# Motors.net
KiCad netlist of a schematic drawn in Altium Designer
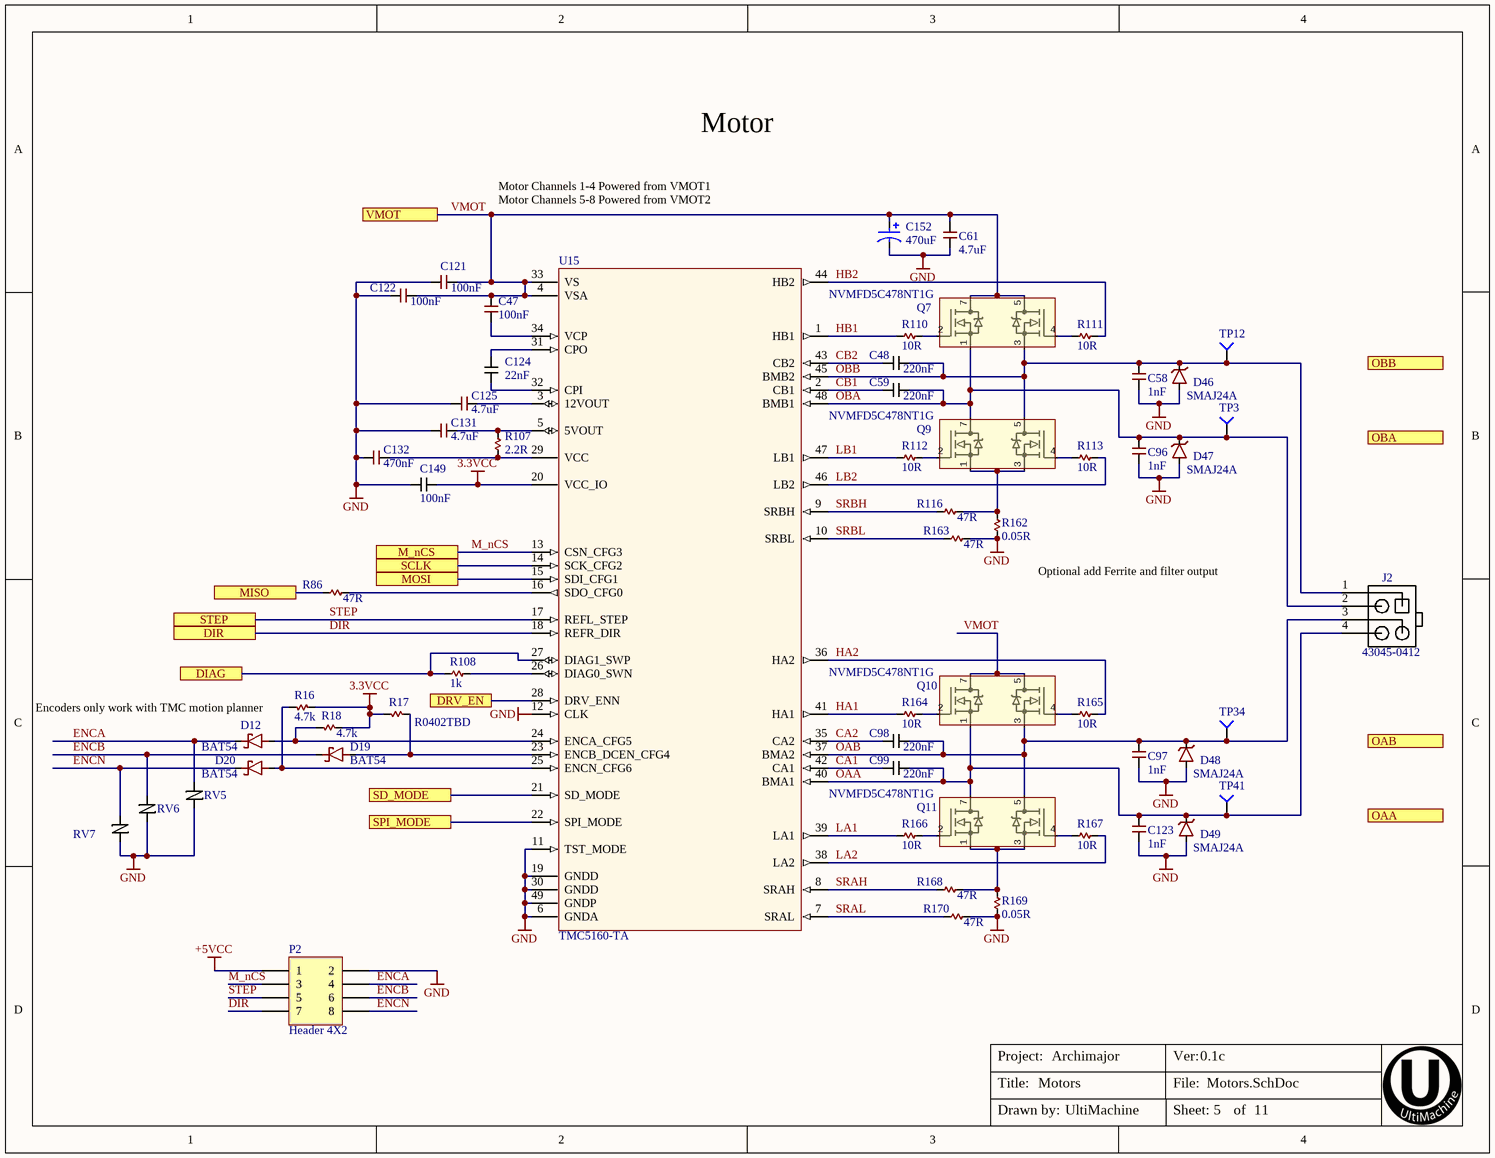
[diagram p0: Motors.SchDoc]

(export (version "E")
  (design (tool "Eeschema 10.0.6"))
  (components
    (comp (ref "C47")
      (value "100nF")
      (footprint "C0603")
      (description "CAP CER 0603 100nF 50V 10% X7R")
      (fields (field (name "MANUFACTURER") "Kemet") (field (name "PART") "C0603C104K5RACTU"))
      (libsource (lib "Capacitors") (part "100nF 0603 50V X7R"))
    )
    (comp (ref "C48")
      (value "220nF")
      (footprint "C0603")
      (description "CAP CER 0.22UF 50V X7R 0603")
      (fields (field (name "MANUFACTURER") "TDK") (field (name "PART") "CGA3E3X7R1H224K080AB"))
      (libsource (lib "Capacitors") (part "220nF 50V X7R 0603"))
    )
    (comp (ref "C58")
      (value "1nF")
      (footprint "C0603")
      (description "CAP CER 0603  1nF 50v 10% X7R")
      (fields (field (name "MANUFACTURER") "Kemet") (field (name "PART") "C0603C102K5RACTU"))
      (libsource (lib "Capacitors") (part "1nF 50V X7R 0603"))
    )
    (comp (ref "C59")
      (value "220nF")
      (footprint "C0603")
      (description "CAP CER 0.22UF 50V X7R 0603")
      (fields (field (name "MANUFACTURER") "TDK") (field (name "PART") "CGA3E3X7R1H224K080AB"))
      (libsource (lib "Capacitors") (part "220nF 50V X7R 0603"))
    )
    (comp (ref "C61")
      (value "4.7uF")
      (footprint "C1206")
      (description "CAP CER 1206 4.7uF 50V 10% X5R")
      (fields (field (name "MANUFACTURER") "Kemet") (field (name "PART") "C1206C475K5PACTU"))
      (libsource (lib "Capacitors") (part "4.7uF 1206 50V X5R"))
    )
    (comp (ref "C96")
      (value "1nF")
      (footprint "C0603")
      (description "CAP CER 0603  1nF 50v 10% X7R")
      (fields (field (name "MANUFACTURER") "Kemet") (field (name "PART") "C0603C102K5RACTU"))
      (libsource (lib "Capacitors") (part "1nF 50V X7R 0603"))
    )
    (comp (ref "C97")
      (value "1nF")
      (footprint "C0603")
      (description "CAP CER 0603  1nF 50v 10% X7R")
      (fields (field (name "MANUFACTURER") "Kemet") (field (name "PART") "C0603C102K5RACTU"))
      (libsource (lib "Capacitors") (part "1nF 50V X7R 0603"))
    )
    (comp (ref "C98")
      (value "220nF")
      (footprint "C0603")
      (description "CAP CER 0.22UF 50V X7R 0603")
      (fields (field (name "MANUFACTURER") "TDK") (field (name "PART") "CGA3E3X7R1H224K080AB"))
      (libsource (lib "Capacitors") (part "220nF 50V X7R 0603"))
    )
    (comp (ref "C99")
      (value "220nF")
      (footprint "C0603")
      (description "CAP CER 0.22UF 50V X7R 0603")
      (fields (field (name "MANUFACTURER") "TDK") (field (name "PART") "CGA3E3X7R1H224K080AB"))
      (libsource (lib "Capacitors") (part "220nF 50V X7R 0603"))
    )
    (comp (ref "C121")
      (value "100nF")
      (footprint "C0603")
      (description "CAP CER 0603 100nF 50V 10% X7R")
      (fields (field (name "MANUFACTURER") "Kemet") (field (name "PART") "C0603C104K5RACTU"))
      (libsource (lib "Capacitors") (part "100nF 0603 50V X7R"))
    )
    (comp (ref "C122")
      (value "100nF")
      (footprint "C0603")
      (description "CAP CER 0603 100nF 50V 10% X7R")
      (fields (field (name "MANUFACTURER") "Kemet") (field (name "PART") "C0603C104K5RACTU"))
      (libsource (lib "Capacitors") (part "100nF 0603 50V X7R"))
    )
    (comp (ref "C123")
      (value "1nF")
      (footprint "C0603")
      (description "CAP CER 0603  1nF 50v 10% X7R")
      (fields (field (name "MANUFACTURER") "Kemet") (field (name "PART") "C0603C102K5RACTU"))
      (libsource (lib "Capacitors") (part "1nF 50V X7R 0603"))
    )
    (comp (ref "C124")
      (value "22nF")
      (footprint "C0603")
      (description "CAP CER 0.022UF 100V X7R 0603")
      (fields (field (name "MANUFACTURER") "Kemet") (field (name "PART") "C0603C223K1RACTU"))
      (libsource (lib "Capacitors") (part "22nF 100V X7R 0603"))
    )
    (comp (ref "C125")
      (value "4.7uF")
      (footprint "C1206")
      (description "CAP CER 1206 4.7uF 50V 10% X5R")
      (fields (field (name "MANUFACTURER") "Kemet") (field (name "PART") "C1206C475K5PACTU"))
      (libsource (lib "Capacitors") (part "4.7uF 1206 50V X5R"))
    )
    (comp (ref "C131")
      (value "4.7uF")
      (footprint "C0603")
      (description "CAP CER 4.7UF 6.3V X7R 0603")
      (fields (field (name "MANUFACTURER") "Samsung") (field (name "PART") "CL10B475KQ8NQNC"))
      (libsource (lib "Capacitors") (part "4.7uF 0603 6.3V X7R"))
    )
    (comp (ref "C132")
      (value "470nF")
      (footprint "C0402")
      (description "470nF 6.3v C0402 - GRM155R60J474KE19D")
      (fields (field (name "TOLERANCE") "10%") (field (name "MANUFACTURER") "Murata"))
      (libsource (lib "Capacitors") (part "470nF 0402 6.3V X5R"))
    )
    (comp (ref "C149")
      (value "100nF")
      (footprint "C0201 Large Pads")
      (description "CAP CER 0.1UF 6.3V 10% X5R 0201")
      (fields (field (name "MANUFACTURER") "Samsung") (field (name "TOLERANCE") "10%"))
      (libsource (lib "Capacitors") (part "100nF 6.3V X5R 0201"))
    )
    (comp (ref "C152")
      (value "470uF")
      (footprint "CAP16x17")
      (description "CAP ALUM 470UF 20% 50V SMD")
      (fields (field (name "MANUFACTURER") "Nichicon") (field (name "PART") "UCZ1H471MNQ1MS"))
      (libsource (lib "Capacitors") (part "470uF Al-El 50V 80mOhms 16-18mmD"))
    )
    (comp (ref "D12")
      (value "BAT54")
      (footprint "SOD523_IPC")
      (description "DIODE SCHOTTKY 30V 200MA SOD523")
      (fields (field (name "MANUFACTURER") "Diodes Incorporated") (field (name "PART") "BAT54WX-TP"))
      (libsource (lib "Diodes") (part "BAT54WX"))
    )
    (comp (ref "D19")
      (value "BAT54")
      (footprint "SOD523_IPC")
      (description "DIODE SCHOTTKY 30V 200MA SOD523")
      (fields (field (name "MANUFACTURER") "Diodes Incorporated") (field (name "PART") "BAT54WX-TP"))
      (libsource (lib "Diodes") (part "BAT54WX"))
    )
    (comp (ref "D20")
      (value "BAT54")
      (footprint "SOD523_IPC")
      (description "DIODE SCHOTTKY 30V 200MA SOD523")
      (fields (field (name "MANUFACTURER") "Diodes Incorporated") (field (name "PART") "BAT54WX-TP"))
      (libsource (lib "Diodes") (part "BAT54WX"))
    )
    (comp (ref "D46")
      (value "SMAJ24A")
      (footprint "SMA-SM")
      (description "TVS DIODE 24V 38.9V SMA")
      (fields (field (name "MANUFACTURER") "Bourns Inc"))
      (libsource (lib "Diodes") (part "SMAJ24A"))
    )
    (comp (ref "D47")
      (value "SMAJ24A")
      (footprint "SMA-SM")
      (description "TVS DIODE 24V 38.9V SMA")
      (fields (field (name "MANUFACTURER") "Bourns Inc"))
      (libsource (lib "Diodes") (part "SMAJ24A"))
    )
    (comp (ref "D48")
      (value "SMAJ24A")
      (footprint "SMA-SM")
      (description "TVS DIODE 24V 38.9V SMA")
      (fields (field (name "MANUFACTURER") "Bourns Inc"))
      (libsource (lib "Diodes") (part "SMAJ24A"))
    )
    (comp (ref "D49")
      (value "SMAJ24A")
      (footprint "SMA-SM")
      (description "TVS DIODE 24V 38.9V SMA")
      (fields (field (name "MANUFACTURER") "Bourns Inc"))
      (libsource (lib "Diodes") (part "SMAJ24A"))
    )
    (comp (ref "J2")
      (value "43045-0412")
      (footprint "43045-0412")
      (description "Conn - 3mm Pitch Fixed")
      (fields (field (name "MANUFACTURER") "Molex"))
      (libsource (lib "Connectors") (part "Micro-Fit THT 4pos 3mm"))
    )
    (comp (ref "P2")
      (value "Header 4X2")
      (footprint "HDR2X4")
      (description "Header, 4-Pin, Dual row")
      (fields (field (name "PUBLISHER") "Altium Limited"))
      (libsource (lib "Miscellaneous Connectors") (part "Header 4X2"))
    )
    (comp (ref "Q7")
      (value "NVMFD5C478NT1G")
      (footprint "SO8FL-Dual (DFN8 5x6, 1.26P Dual Flag)")
      (description "40V 17 MOHM T6 S08FL DUAL")
      (fields (field (name "MANUFACTURER") "ON Semiconductor") (field (name "TOLERANCE") "-NA-"))
      (libsource (lib "Transistors") (part "NVMFD5C478NT1G"))
    )
    (comp (ref "Q9")
      (value "NVMFD5C478NT1G")
      (footprint "SO8FL-Dual (DFN8 5x6, 1.26P Dual Flag)")
      (description "40V 17 MOHM T6 S08FL DUAL")
      (fields (field (name "MANUFACTURER") "ON Semiconductor") (field (name "TOLERANCE") "-NA-"))
      (libsource (lib "Transistors") (part "NVMFD5C478NT1G"))
    )
    (comp (ref "Q10")
      (value "NVMFD5C478NT1G")
      (footprint "SO8FL-Dual (DFN8 5x6, 1.26P Dual Flag)")
      (description "40V 17 MOHM T6 S08FL DUAL")
      (fields (field (name "MANUFACTURER") "ON Semiconductor") (field (name "TOLERANCE") "-NA-"))
      (libsource (lib "Transistors") (part "NVMFD5C478NT1G"))
    )
    (comp (ref "Q11")
      (value "NVMFD5C478NT1G")
      (footprint "SO8FL-Dual (DFN8 5x6, 1.26P Dual Flag)")
      (description "40V 17 MOHM T6 S08FL DUAL")
      (fields (field (name "MANUFACTURER") "ON Semiconductor") (field (name "TOLERANCE") "-NA-"))
      (libsource (lib "Transistors") (part "NVMFD5C478NT1G"))
    )
    (comp (ref "R16")
      (value "4.7k")
      (footprint "R0402")
      (description "RES SMD 4.7K OHM 1% 1/16W 0402")
      (fields (field (name "MANUFACTURER") "YAGEO") (field (name "PART") "RC0402FR-074K7L"))
      (libsource (lib "Resistors") (part "4.7k 1% 0402"))
    )
    (comp (ref "R17")
      (value "R0402TBD")
      (footprint "R0402")
      (description "Resistor")
      (libsource (lib "Resistors") (part "R0402TBD"))
    )
    (comp (ref "R18")
      (value "4.7k")
      (footprint "R0402")
      (description "RES SMD 4.7K OHM 1% 1/16W 0402")
      (fields (field (name "MANUFACTURER") "YAGEO") (field (name "PART") "RC0402FR-074K7L"))
      (libsource (lib "Resistors") (part "4.7k 1% 0402"))
    )
    (comp (ref "R86")
      (value "47R")
      (footprint "R0402")
      (description "RES 47 OHM 1% 1/16W 0402")
      (fields (field (name "MANUFACTURER") "Vishay Dale") (field (name "TOLERANCE") "+/- 1%"))
      (libsource (lib "Resistors") (part "47R 1% 0402"))
    )
    (comp (ref "R107")
      (value "2.2R")
      (footprint "R0402")
      (description "RES SMD 2.2 OHM 5% 1/16W 0402")
      (fields (field (name "MANUFACTURER") "Yageo") (field (name "TOLERANCE") "+/- 5%"))
      (libsource (lib "Resistors") (part "2.2R 5% 0402"))
    )
    (comp (ref "R108")
      (value "1k")
      (footprint "R0402")
      (description "RES 0402 1k 63mW 1%")
      (fields (field (name "MANUFACTURER") "Yageo") (field (name "PART") "RC0402FR-071KL"))
      (libsource (lib "Resistors") (part "1k 1% 0402"))
    )
    (comp (ref "R110")
      (value "10R")
      (footprint "R0402")
      (description "RES SMD 10 OHM 1% 1/16W 0402")
      (fields (field (name "MANUFACTURER") "Yageo") (field (name "PART") "RC0402FR-0710RL"))
      (libsource (lib "Resistors") (part "10R 1% 0402"))
    )
    (comp (ref "R111")
      (value "10R")
      (footprint "R0402")
      (description "RES SMD 10 OHM 1% 1/16W 0402")
      (fields (field (name "MANUFACTURER") "Yageo") (field (name "PART") "RC0402FR-0710RL"))
      (libsource (lib "Resistors") (part "10R 1% 0402"))
    )
    (comp (ref "R112")
      (value "10R")
      (footprint "R0402")
      (description "RES SMD 10 OHM 1% 1/16W 0402")
      (fields (field (name "MANUFACTURER") "Yageo") (field (name "PART") "RC0402FR-0710RL"))
      (libsource (lib "Resistors") (part "10R 1% 0402"))
    )
    (comp (ref "R113")
      (value "10R")
      (footprint "R0402")
      (description "RES SMD 10 OHM 1% 1/16W 0402")
      (fields (field (name "MANUFACTURER") "Yageo") (field (name "PART") "RC0402FR-0710RL"))
      (libsource (lib "Resistors") (part "10R 1% 0402"))
    )
    (comp (ref "R116")
      (value "47R")
      (footprint "R0402")
      (description "RES 47 OHM 1% 1/16W 0402")
      (fields (field (name "MANUFACTURER") "Vishay Dale") (field (name "TOLERANCE") "+/- 1%"))
      (libsource (lib "Resistors") (part "47R 1% 0402"))
    )
    (comp (ref "R162")
      (value "0.05R")
      (footprint "R2512")
      (description "RES 0.05 OHM 1% 2W 2512")
      (fields (field (name "MANUFACTURER") "Stackpole") (field (name "TOLERANCE") "+/- 1%"))
      (libsource (lib "Resistors") (part "0.05R 1% 2512"))
    )
    (comp (ref "R163")
      (value "47R")
      (footprint "R0402")
      (description "RES 47 OHM 1% 1/16W 0402")
      (fields (field (name "MANUFACTURER") "Vishay Dale") (field (name "TOLERANCE") "+/- 1%"))
      (libsource (lib "Resistors") (part "47R 1% 0402"))
    )
    (comp (ref "R164")
      (value "10R")
      (footprint "R0402")
      (description "RES SMD 10 OHM 1% 1/16W 0402")
      (fields (field (name "MANUFACTURER") "Yageo") (field (name "PART") "RC0402FR-0710RL"))
      (libsource (lib "Resistors") (part "10R 1% 0402"))
    )
    (comp (ref "R165")
      (value "10R")
      (footprint "R0402")
      (description "RES SMD 10 OHM 1% 1/16W 0402")
      (fields (field (name "MANUFACTURER") "Yageo") (field (name "PART") "RC0402FR-0710RL"))
      (libsource (lib "Resistors") (part "10R 1% 0402"))
    )
    (comp (ref "R166")
      (value "10R")
      (footprint "R0402")
      (description "RES SMD 10 OHM 1% 1/16W 0402")
      (fields (field (name "MANUFACTURER") "Yageo") (field (name "PART") "RC0402FR-0710RL"))
      (libsource (lib "Resistors") (part "10R 1% 0402"))
    )
    (comp (ref "R167")
      (value "10R")
      (footprint "R0402")
      (description "RES SMD 10 OHM 1% 1/16W 0402")
      (fields (field (name "MANUFACTURER") "Yageo") (field (name "PART") "RC0402FR-0710RL"))
      (libsource (lib "Resistors") (part "10R 1% 0402"))
    )
    (comp (ref "R168")
      (value "47R")
      (footprint "R0402")
      (description "RES 47 OHM 1% 1/16W 0402")
      (fields (field (name "MANUFACTURER") "Vishay Dale") (field (name "TOLERANCE") "+/- 1%"))
      (libsource (lib "Resistors") (part "47R 1% 0402"))
    )
    (comp (ref "R169")
      (value "0.05R")
      (footprint "R2512")
      (description "RES 0.05 OHM 1% 2W 2512")
      (fields (field (name "MANUFACTURER") "Stackpole") (field (name "TOLERANCE") "+/- 1%"))
      (libsource (lib "Resistors") (part "0.05R 1% 2512"))
    )
    (comp (ref "R170")
      (value "47R")
      (footprint "R0402")
      (description "RES 47 OHM 1% 1/16W 0402")
      (fields (field (name "MANUFACTURER") "Vishay Dale") (field (name "TOLERANCE") "+/- 1%"))
      (libsource (lib "Resistors") (part "47R 1% 0402"))
    )
    (comp (ref "RV5")
      (value "AVRM0603C6R8NT101N")
      (footprint "C0201 Large Pads")
      (description "VARISTOR 6.8V 10A 0201")
      (fields (field (name "MANUFACTURER") "TDK") (field (name "TOLERANCE") "-NA-"))
      (libsource (lib "ESD") (part "AVRM0603C6R8NT101N"))
    )
    (comp (ref "RV6")
      (value "AVRM0603C6R8NT101N")
      (footprint "C0201 Large Pads")
      (description "VARISTOR 6.8V 10A 0201")
      (fields (field (name "MANUFACTURER") "TDK") (field (name "TOLERANCE") "-NA-"))
      (libsource (lib "ESD") (part "AVRM0603C6R8NT101N"))
    )
    (comp (ref "RV7")
      (value "AVRM0603C6R8NT101N")
      (footprint "C0201 Large Pads")
      (description "VARISTOR 6.8V 10A 0201")
      (fields (field (name "MANUFACTURER") "TDK") (field (name "TOLERANCE") "-NA-"))
      (libsource (lib "ESD") (part "AVRM0603C6R8NT101N"))
    )
    (comp (ref "TP3")
      (value "TP4")
      (footprint "TP-2")
      (description "Socket")
      (fields (field (name "PART") "NOTAPART-Testpoint"))
      (libsource (lib "Archim") (part "Socket"))
    )
    (comp (ref "TP12")
      (value "TP4")
      (footprint "TP-2")
      (description "Socket")
      (fields (field (name "PART") "NOTAPART-Testpoint"))
      (libsource (lib "Archim") (part "Socket"))
    )
    (comp (ref "TP34")
      (value "TP4")
      (footprint "TP-2")
      (description "Socket")
      (fields (field (name "PART") "NOTAPART-Testpoint"))
      (libsource (lib "Archim") (part "Socket"))
    )
    (comp (ref "TP41")
      (value "TP4")
      (footprint "TP-2")
      (description "Socket")
      (fields (field (name "PART") "NOTAPART-Testpoint"))
      (libsource (lib "Archim") (part "Socket"))
    )
    (comp (ref "U15")
      (value "TMC5160-TA")
      (footprint "TQFP48-EP")
      (description "IC STEPPER MOTOR DVR TQFP48-EP")
      (fields (field (name "MANUFACTURER") "Trinamic"))
      (libsource (lib "ICs-Motor Controller") (part "TMC5160-TA"))
    )
  )
  (nets
    (net (code "1") (name "+5VCC") (class "Default")
      (node (ref "P2") (pin "1") (pinfunction "1_1") (pintype "passive"))
    )
    (net (code "2") (name "/CA1") (class "Default")
      (node (ref "C99") (pin "1") (pinfunction "1_1") (pintype "passive"))
      (node (ref "U15") (pin "42") (pinfunction "CA1_42") (pintype "input"))
    )
    (net (code "3") (name "/CA2") (class "Default")
      (node (ref "C98") (pin "1") (pinfunction "1_1") (pintype "passive"))
      (node (ref "U15") (pin "35") (pinfunction "CA2_35") (pintype "input"))
    )
    (net (code "4") (name "/CB1") (class "Default")
      (node (ref "C59") (pin "1") (pinfunction "1_1") (pintype "passive"))
      (node (ref "U15") (pin "2") (pinfunction "CB1_2") (pintype "input"))
    )
    (net (code "5") (name "/CB2") (class "Default")
      (node (ref "C48") (pin "1") (pinfunction "1_1") (pintype "passive"))
      (node (ref "U15") (pin "43") (pinfunction "CB2_43") (pintype "input"))
    )
    (net (code "6") (name "/DIAG") (class "Default")
      (node (ref "R108") (pin "2") (pinfunction "2_2") (pintype "passive"))
      (node (ref "U15") (pin "27") (pinfunction "DIAG1_SWP_27") (pintype "bidirectional"))
    )
    (net (code "7") (name "/DIR") (class "Default")
      (node (ref "P2") (pin "7") (pinfunction "7_7") (pintype "passive"))
      (node (ref "U15") (pin "18") (pinfunction "REFR_DIR_18") (pintype "input"))
    )
    (net (code "8") (name "/DRV_EN") (class "Default")
      (node (ref "U15") (pin "28") (pinfunction "DRV_ENN_28") (pintype "input"))
    )
    (net (code "9") (name "/ENCA") (class "Default")
      (node (ref "D12") (pin "K") (pinfunction "K_K") (pintype "passive"))
      (node (ref "P2") (pin "4") (pinfunction "4_4") (pintype "passive"))
      (node (ref "RV5") (pin "1") (pinfunction "1_1") (pintype "power_in"))
    )
    (net (code "10") (name "/ENCB") (class "Default")
      (node (ref "D19") (pin "K") (pinfunction "K_K") (pintype "passive"))
      (node (ref "P2") (pin "6") (pinfunction "6_6") (pintype "passive"))
      (node (ref "RV6") (pin "1") (pinfunction "1_1") (pintype "power_in"))
    )
    (net (code "11") (name "/ENCN") (class "Default")
      (node (ref "D20") (pin "K") (pinfunction "K_K") (pintype "passive"))
      (node (ref "P2") (pin "8") (pinfunction "8_8") (pintype "passive"))
      (node (ref "RV7") (pin "1") (pinfunction "1_1") (pintype "power_in"))
    )
    (net (code "12") (name "/HA1") (class "Default")
      (node (ref "R164") (pin "1") (pinfunction "1_1") (pintype "passive"))
      (node (ref "U15") (pin "41") (pinfunction "HA1_41") (pintype "output"))
    )
    (net (code "13") (name "/HA2") (class "Default")
      (node (ref "R165") (pin "2") (pinfunction "2_2") (pintype "passive"))
      (node (ref "U15") (pin "36") (pinfunction "HA2_36") (pintype "output"))
    )
    (net (code "14") (name "/HB1") (class "Default")
      (node (ref "R110") (pin "1") (pinfunction "1_1") (pintype "passive"))
      (node (ref "U15") (pin "1") (pinfunction "HB1_1") (pintype "output"))
    )
    (net (code "15") (name "/HB2") (class "Default")
      (node (ref "R111") (pin "2") (pinfunction "2_2") (pintype "passive"))
      (node (ref "U15") (pin "44") (pinfunction "HB2_44") (pintype "output"))
    )
    (net (code "16") (name "/LA1") (class "Default")
      (node (ref "R166") (pin "1") (pinfunction "1_1") (pintype "passive"))
      (node (ref "U15") (pin "39") (pinfunction "LA1_39") (pintype "output"))
    )
    (net (code "17") (name "/LA2") (class "Default")
      (node (ref "R167") (pin "2") (pinfunction "2_2") (pintype "passive"))
      (node (ref "U15") (pin "38") (pinfunction "LA2_38") (pintype "output"))
    )
    (net (code "18") (name "/LB1") (class "Default")
      (node (ref "R112") (pin "1") (pinfunction "1_1") (pintype "passive"))
      (node (ref "U15") (pin "47") (pinfunction "LB1_47") (pintype "output"))
    )
    (net (code "19") (name "/LB2") (class "Default")
      (node (ref "R113") (pin "2") (pinfunction "2_2") (pintype "passive"))
      (node (ref "U15") (pin "46") (pinfunction "LB2_46") (pintype "output"))
    )
    (net (code "20") (name "/MISO") (class "Default")
      (node (ref "R86") (pin "1") (pinfunction "1_1") (pintype "passive"))
    )
    (net (code "21") (name "/MOSI") (class "Default")
      (node (ref "U15") (pin "15") (pinfunction "SDI_CFG1_15") (pintype "input"))
    )
    (net (code "22") (name "/M_nCS") (class "Default")
      (node (ref "P2") (pin "3") (pinfunction "3_3") (pintype "passive"))
      (node (ref "U15") (pin "13") (pinfunction "CSN_CFG3_13") (pintype "input"))
    )
    (net (code "23") (name "/OAA") (class "Default")
      (node (ref "C123") (pin "2") (pinfunction "2_2") (pintype "passive"))
      (node (ref "C99") (pin "2") (pinfunction "2_2") (pintype "passive"))
      (node (ref "D49") (pin "K") (pinfunction "K_K") (pintype "passive"))
      (node (ref "J2") (pin "4") (pinfunction "4_4") (pintype "power_in"))
      (node (ref "Q10") (pin "1") (pinfunction "S2_1") (pintype "passive"))
      (node (ref "Q11") (pin "7") (pinfunction "D2_7") (pintype "passive"))
      (node (ref "TP41") (pin "1") (pinfunction "1_1") (pintype "passive"))
      (node (ref "U15") (pin "40") (pinfunction "BMA1_40") (pintype "input"))
    )
    (net (code "24") (name "/OAB") (class "Default")
      (node (ref "C97") (pin "2") (pinfunction "2_2") (pintype "passive"))
      (node (ref "C98") (pin "2") (pinfunction "2_2") (pintype "passive"))
      (node (ref "D48") (pin "K") (pinfunction "K_K") (pintype "passive"))
      (node (ref "J2") (pin "3") (pinfunction "3_3") (pintype "power_in"))
      (node (ref "Q10") (pin "3") (pinfunction "S1_3") (pintype "passive"))
      (node (ref "Q11") (pin "5") (pinfunction "D1_5") (pintype "passive"))
      (node (ref "TP34") (pin "1") (pinfunction "1_1") (pintype "passive"))
      (node (ref "U15") (pin "37") (pinfunction "BMA2_37") (pintype "input"))
    )
    (net (code "25") (name "/OBA") (class "Default")
      (node (ref "C59") (pin "2") (pinfunction "2_2") (pintype "passive"))
      (node (ref "C96") (pin "2") (pinfunction "2_2") (pintype "passive"))
      (node (ref "D47") (pin "K") (pinfunction "K_K") (pintype "passive"))
      (node (ref "J2") (pin "2") (pinfunction "2_2") (pintype "power_in"))
      (node (ref "Q7") (pin "1") (pinfunction "S2_1") (pintype "passive"))
      (node (ref "Q9") (pin "7") (pinfunction "D2_7") (pintype "passive"))
      (node (ref "TP3") (pin "1") (pinfunction "1_1") (pintype "passive"))
      (node (ref "U15") (pin "48") (pinfunction "BMB1_48") (pintype "input"))
    )
    (net (code "26") (name "/OBB") (class "Default")
      (node (ref "C48") (pin "2") (pinfunction "2_2") (pintype "passive"))
      (node (ref "C58") (pin "2") (pinfunction "2_2") (pintype "passive"))
      (node (ref "D46") (pin "K") (pinfunction "K_K") (pintype "passive"))
      (node (ref "J2") (pin "1") (pinfunction "1_1") (pintype "power_in"))
      (node (ref "Q7") (pin "3") (pinfunction "S1_3") (pintype "passive"))
      (node (ref "Q9") (pin "5") (pinfunction "D1_5") (pintype "passive"))
      (node (ref "TP12") (pin "1") (pinfunction "1_1") (pintype "passive"))
      (node (ref "U15") (pin "45") (pinfunction "BMB2_45") (pintype "input"))
    )
    (net (code "27") (name "/SCLK") (class "Default")
      (node (ref "U15") (pin "14") (pinfunction "SCK_CFG2_14") (pintype "input"))
    )
    (net (code "28") (name "/SD_MODE") (class "Default")
      (node (ref "U15") (pin "21") (pinfunction "SD_MODE_21") (pintype "input"))
    )
    (net (code "29") (name "/SPI_MODE") (class "Default")
      (node (ref "U15") (pin "22") (pinfunction "SPI_MODE_22") (pintype "input"))
    )
    (net (code "30") (name "/SRAH") (class "Default")
      (node (ref "R168") (pin "1") (pinfunction "1_1") (pintype "passive"))
      (node (ref "U15") (pin "8") (pinfunction "SRAH_8") (pintype "input"))
    )
    (net (code "31") (name "/SRAL") (class "Default")
      (node (ref "R170") (pin "1") (pinfunction "1_1") (pintype "passive"))
      (node (ref "U15") (pin "7") (pinfunction "SRAL_7") (pintype "input"))
    )
    (net (code "32") (name "/SRBH") (class "Default")
      (node (ref "R116") (pin "1") (pinfunction "1_1") (pintype "passive"))
      (node (ref "U15") (pin "9") (pinfunction "SRBH_9") (pintype "input"))
    )
    (net (code "33") (name "/SRBL") (class "Default")
      (node (ref "R163") (pin "1") (pinfunction "1_1") (pintype "passive"))
      (node (ref "U15") (pin "10") (pinfunction "SRBL_10") (pintype "input"))
    )
    (net (code "34") (name "/STEP") (class "Default")
      (node (ref "P2") (pin "5") (pinfunction "5_5") (pintype "passive"))
      (node (ref "U15") (pin "17") (pinfunction "REFL_STEP_17") (pintype "input"))
    )
    (net (code "35") (name "/VMOT") (class "Default")
      (node (ref "C121") (pin "2") (pinfunction "2_2") (pintype "passive"))
      (node (ref "C122") (pin "2") (pinfunction "2_2") (pintype "passive"))
      (node (ref "C152") (pin "1") (pinfunction "1_1") (pintype "passive"))
      (node (ref "C47") (pin "2") (pinfunction "2_2") (pintype "passive"))
      (node (ref "C61") (pin "2") (pinfunction "2_2") (pintype "passive"))
      (node (ref "Q10") (pin "5") (pinfunction "D1_5") (pintype "passive"))
      (node (ref "Q10") (pin "7") (pinfunction "D2_7") (pintype "passive"))
      (node (ref "Q7") (pin "5") (pinfunction "D1_5") (pintype "passive"))
      (node (ref "Q7") (pin "7") (pinfunction "D2_7") (pintype "passive"))
      (node (ref "U15") (pin "33") (pinfunction "VS_33") (pintype "power_in"))
      (node (ref "U15") (pin "4") (pinfunction "VSA_4") (pintype "power_in"))
    )
    (net (code "36") (name "3.3VCC") (class "Default")
      (node (ref "C149") (pin "2") (pinfunction "2_2") (pintype "passive"))
      (node (ref "R16") (pin "2") (pinfunction "2_2") (pintype "passive"))
      (node (ref "R17") (pin "1") (pinfunction "1_1") (pintype "passive"))
      (node (ref "R18") (pin "2") (pinfunction "2_2") (pintype "passive"))
      (node (ref "U15") (pin "20") (pinfunction "VCC_IO_20") (pintype "power_in"))
    )
    (net (code "37") (name "GND") (class "Default")
      (node (ref "C121") (pin "1") (pinfunction "1_1") (pintype "passive"))
      (node (ref "C122") (pin "1") (pinfunction "1_1") (pintype "passive"))
      (node (ref "C123") (pin "1") (pinfunction "1_1") (pintype "passive"))
      (node (ref "C125") (pin "1") (pinfunction "1_1") (pintype "passive"))
      (node (ref "C131") (pin "1") (pinfunction "1_1") (pintype "passive"))
      (node (ref "C132") (pin "1") (pinfunction "1_1") (pintype "passive"))
      (node (ref "C149") (pin "1") (pinfunction "1_1") (pintype "passive"))
      (node (ref "C152") (pin "2") (pinfunction "2_2") (pintype "passive"))
      (node (ref "C58") (pin "1") (pinfunction "1_1") (pintype "passive"))
      (node (ref "C61") (pin "1") (pinfunction "1_1") (pintype "passive"))
      (node (ref "C96") (pin "1") (pinfunction "1_1") (pintype "passive"))
      (node (ref "C97") (pin "1") (pinfunction "1_1") (pintype "passive"))
      (node (ref "D46") (pin "A") (pinfunction "A_A") (pintype "passive"))
      (node (ref "D47") (pin "A") (pinfunction "A_A") (pintype "passive"))
      (node (ref "D48") (pin "A") (pinfunction "A_A") (pintype "passive"))
      (node (ref "D49") (pin "A") (pinfunction "A_A") (pintype "passive"))
      (node (ref "P2") (pin "2") (pinfunction "2_2") (pintype "passive"))
      (node (ref "R162") (pin "1") (pinfunction "1_1") (pintype "passive"))
      (node (ref "R163") (pin "2") (pinfunction "2_2") (pintype "passive"))
      (node (ref "R169") (pin "1") (pinfunction "1_1") (pintype "passive"))
      (node (ref "R170") (pin "2") (pinfunction "2_2") (pintype "passive"))
      (node (ref "RV5") (pin "2") (pinfunction "2_2") (pintype "power_in"))
      (node (ref "RV6") (pin "2") (pinfunction "2_2") (pintype "power_in"))
      (node (ref "RV7") (pin "2") (pinfunction "2_2") (pintype "power_in"))
      (node (ref "U15") (pin "11") (pinfunction "TST_MODE_11") (pintype "input"))
      (node (ref "U15") (pin "12") (pinfunction "CLK_12") (pintype "input"))
      (node (ref "U15") (pin "19") (pinfunction "GNDD_19") (pintype "power_in"))
      (node (ref "U15") (pin "30") (pinfunction "GNDD_30") (pintype "power_in"))
      (node (ref "U15") (pin "49") (pinfunction "GNDP_49") (pintype "power_in"))
      (node (ref "U15") (pin "6") (pinfunction "GNDA_6") (pintype "power_in"))
    )
    (net (code "38") (name "Net-(Q7-G1)") (class "Default")
      (node (ref "Q7") (pin "4") (pinfunction "G1_4") (pintype "passive"))
      (node (ref "R111") (pin "1") (pinfunction "1_1") (pintype "passive"))
    )
    (net (code "39") (name "Net-(Q7-G2)") (class "Default")
      (node (ref "Q7") (pin "2") (pinfunction "G2_2") (pintype "passive"))
      (node (ref "R110") (pin "2") (pinfunction "2_2") (pintype "passive"))
    )
    (net (code "40") (name "Net-(Q9-G1)") (class "Default")
      (node (ref "Q9") (pin "4") (pinfunction "G1_4") (pintype "passive"))
      (node (ref "R113") (pin "1") (pinfunction "1_1") (pintype "passive"))
    )
    (net (code "41") (name "Net-(Q9-G2)") (class "Default")
      (node (ref "Q9") (pin "2") (pinfunction "G2_2") (pintype "passive"))
      (node (ref "R112") (pin "2") (pinfunction "2_2") (pintype "passive"))
    )
    (net (code "42") (name "Net-(Q9-S1)") (class "Default")
      (node (ref "Q9") (pin "1") (pinfunction "S2_1") (pintype "passive"))
      (node (ref "Q9") (pin "3") (pinfunction "S1_3") (pintype "passive"))
      (node (ref "R116") (pin "2") (pinfunction "2_2") (pintype "passive"))
      (node (ref "R162") (pin "2") (pinfunction "2_2") (pintype "passive"))
    )
    (net (code "43") (name "Net-(Q10-G1)") (class "Default")
      (node (ref "Q10") (pin "4") (pinfunction "G1_4") (pintype "passive"))
      (node (ref "R165") (pin "1") (pinfunction "1_1") (pintype "passive"))
    )
    (net (code "44") (name "Net-(Q10-G2)") (class "Default")
      (node (ref "Q10") (pin "2") (pinfunction "G2_2") (pintype "passive"))
      (node (ref "R164") (pin "2") (pinfunction "2_2") (pintype "passive"))
    )
    (net (code "45") (name "Net-(Q11-G1)") (class "Default")
      (node (ref "Q11") (pin "4") (pinfunction "G1_4") (pintype "passive"))
      (node (ref "R167") (pin "1") (pinfunction "1_1") (pintype "passive"))
    )
    (net (code "46") (name "Net-(Q11-G2)") (class "Default")
      (node (ref "Q11") (pin "2") (pinfunction "G2_2") (pintype "passive"))
      (node (ref "R166") (pin "2") (pinfunction "2_2") (pintype "passive"))
    )
    (net (code "47") (name "Net-(Q11-S1)") (class "Default")
      (node (ref "Q11") (pin "1") (pinfunction "S2_1") (pintype "passive"))
      (node (ref "Q11") (pin "3") (pinfunction "S1_3") (pintype "passive"))
      (node (ref "R168") (pin "2") (pinfunction "2_2") (pintype "passive"))
      (node (ref "R169") (pin "2") (pinfunction "2_2") (pintype "passive"))
    )
    (net (code "48") (name "Net-(U15-5VOUT)") (class "Default")
      (node (ref "C131") (pin "2") (pinfunction "2_2") (pintype "passive"))
      (node (ref "R107") (pin "2") (pinfunction "2_2") (pintype "passive"))
      (node (ref "U15") (pin "5") (pinfunction "5VOUT_5") (pintype "bidirectional"))
    )
    (net (code "49") (name "Net-(U15-12VOUT)") (class "Default")
      (node (ref "C125") (pin "2") (pinfunction "2_2") (pintype "passive"))
      (node (ref "U15") (pin "3") (pinfunction "12VOUT_3") (pintype "bidirectional"))
    )
    (net (code "50") (name "Net-(U15-CPI)") (class "Default")
      (node (ref "C124") (pin "1") (pinfunction "1_1") (pintype "passive"))
      (node (ref "U15") (pin "32") (pinfunction "CPI_32") (pintype "input"))
    )
    (net (code "51") (name "Net-(U15-CPO)") (class "Default")
      (node (ref "C124") (pin "2") (pinfunction "2_2") (pintype "passive"))
      (node (ref "U15") (pin "31") (pinfunction "CPO_31") (pintype "input"))
    )
    (net (code "52") (name "Net-(U15-DIAG0_SWN)") (class "Default")
      (node (ref "R108") (pin "1") (pinfunction "1_1") (pintype "passive"))
      (node (ref "U15") (pin "26") (pinfunction "DIAG0_SWN_26") (pintype "bidirectional"))
    )
    (net (code "53") (name "Net-(U15-ENCA_CFG5)") (class "Default")
      (node (ref "D12") (pin "A") (pinfunction "A_A") (pintype "passive"))
      (node (ref "R18") (pin "1") (pinfunction "1_1") (pintype "passive"))
      (node (ref "U15") (pin "24") (pinfunction "ENCA_CFG5_24") (pintype "input"))
    )
    (net (code "54") (name "Net-(U15-ENCB_DCEN_CFG4)") (class "Default")
      (node (ref "D19") (pin "A") (pinfunction "A_A") (pintype "passive"))
      (node (ref "R17") (pin "2") (pinfunction "2_2") (pintype "passive"))
      (node (ref "U15") (pin "23") (pinfunction "ENCB_DCEN_CFG4_23") (pintype "input"))
    )
    (net (code "55") (name "Net-(U15-ENCN_CFG6)") (class "Default")
      (node (ref "D20") (pin "A") (pinfunction "A_A") (pintype "passive"))
      (node (ref "R16") (pin "1") (pinfunction "1_1") (pintype "passive"))
      (node (ref "U15") (pin "25") (pinfunction "ENCN_CFG6_25") (pintype "input"))
    )
    (net (code "56") (name "Net-(U15-SDO_CFG0)") (class "Default")
      (node (ref "R86") (pin "2") (pinfunction "2_2") (pintype "passive"))
      (node (ref "U15") (pin "16") (pinfunction "SDO_CFG0_16") (pintype "output"))
    )
    (net (code "57") (name "Net-(U15-VCC)") (class "Default")
      (node (ref "C132") (pin "2") (pinfunction "2_2") (pintype "passive"))
      (node (ref "R107") (pin "1") (pinfunction "1_1") (pintype "passive"))
      (node (ref "U15") (pin "29") (pinfunction "VCC_29") (pintype "power_in"))
    )
    (net (code "58") (name "Net-(U15-VCP)") (class "Default")
      (node (ref "C47") (pin "1") (pinfunction "1_1") (pintype "passive"))
      (node (ref "U15") (pin "34") (pinfunction "VCP_34") (pintype "input"))
    )
  )
)
